# STM32.net
KiCad netlist of a schematic drawn in EasyEDA Pro
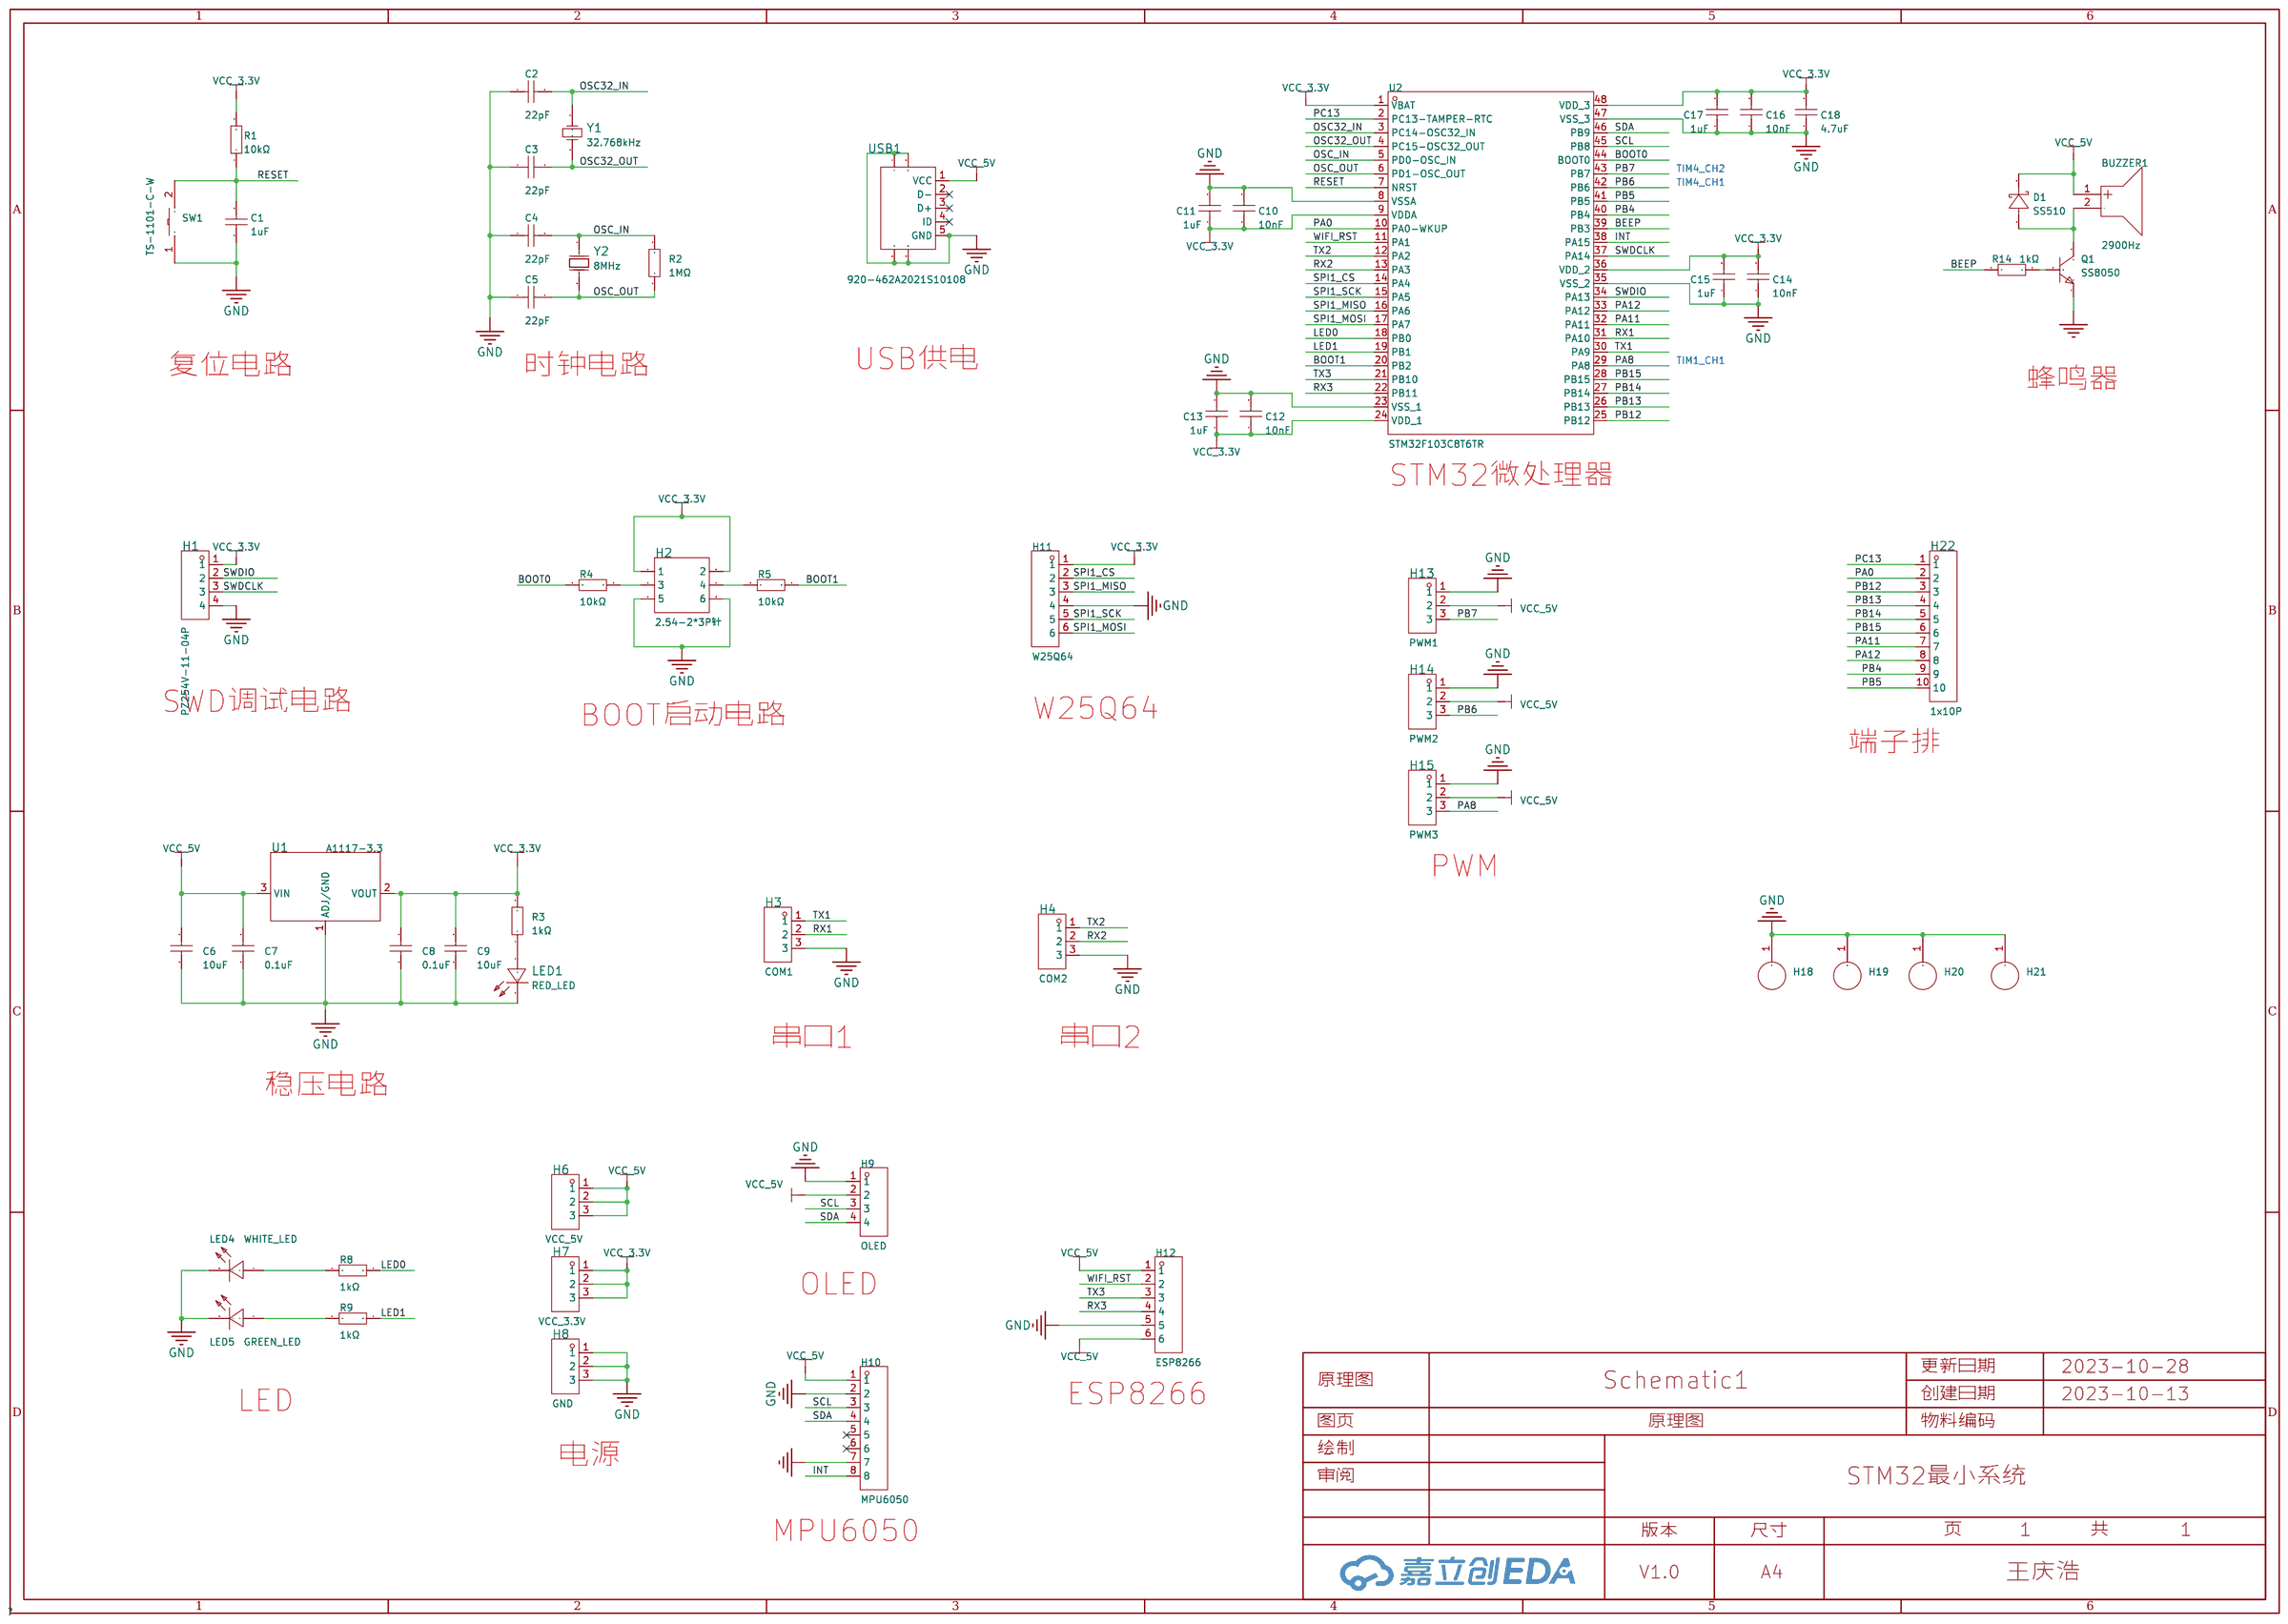
[diagram p0: schematic sheet]

(export (version "E")
  (design (tool "Eeschema 10.0.6"))
  (components
    (comp (ref "BUZZER1")
      (value "2900Hz")
      (footprint "easyedapro:BUZ-TH_BD9.6-P5.00-D0.7-FD")
      (description "驱动方式:有源(内含驱动线路);构造类型:电磁式;额定电压:5V;工作电压:4V~7V;频率:2900Hz;声压(SPL):85dB@5V,10cm;直径(φD):9.6mm;高度:5.5mm;")
      (fields (field (name "Manufacturer Part") "Cy-9650-5029") (field (name "Manufacturer") "CY(超音)"))
      (libsource (lib "easyedapro") (part "CY-9650-5029"))
    )
    (comp (ref "C1")
      (value "1uF")
      (footprint "easyedapro:C0805")
      (description "容值:1uF;精度:±10%;额定电压:50V;材质(温度系数):X7R;")
      (fields
        (field (name "Manufacturer Part") "CL21B105KBFNNNE")
        (field (name "Manufacturer") "SAMSUNG(三星)")
      )
      (libsource (lib "easyedapro") (part "CL21B105KBFNNNE"))
    )
    (comp (ref "C2")
      (value "22pF")
      (footprint "easyedapro:C0805")
      (description "容值:22pF;精度:±5%;额定电压:50V;材质(温度系数):C0G;")
      (fields
        (field (name "Manufacturer Part") "CL21C220JBANNNC")
        (field (name "Manufacturer") "SAMSUNG(三星)")
      )
      (libsource (lib "easyedapro") (part "CL21C220JBANNNC"))
    )
    (comp (ref "C3")
      (value "22pF")
      (footprint "easyedapro:C0805")
      (description "容值:22pF;精度:±5%;额定电压:50V;材质(温度系数):C0G;")
      (fields
        (field (name "Manufacturer Part") "CL21C220JBANNNC")
        (field (name "Manufacturer") "SAMSUNG(三星)")
      )
      (libsource (lib "easyedapro") (part "CL21C220JBANNNC"))
    )
    (comp (ref "C4")
      (value "22pF")
      (footprint "easyedapro:C0805")
      (description "容值:22pF;精度:±5%;额定电压:50V;材质(温度系数):C0G;")
      (fields
        (field (name "Manufacturer Part") "CL21C220JBANNNC")
        (field (name "Manufacturer") "SAMSUNG(三星)")
      )
      (libsource (lib "easyedapro") (part "CL21C220JBANNNC"))
    )
    (comp (ref "C5")
      (value "22pF")
      (footprint "easyedapro:C0805")
      (description "容值:22pF;精度:±5%;额定电压:50V;材质(温度系数):C0G;")
      (fields
        (field (name "Manufacturer Part") "CL21C220JBANNNC")
        (field (name "Manufacturer") "SAMSUNG(三星)")
      )
      (libsource (lib "easyedapro") (part "CL21C220JBANNNC"))
    )
    (comp (ref "C6")
      (value "10uF")
      (footprint "easyedapro:C0805")
      (description "容值:100nF;精度:±10%;额定电压:50V;材质(温度系数):X7R;")
      (fields
        (field (name "Manufacturer Part") "CC0805KRX7R9BB104")
        (field (name "Manufacturer") "YAGEO(国巨)")
      )
      (libsource (lib "easyedapro") (part "CC0805KRX7R9BB104"))
    )
    (comp (ref "C7")
      (value "0.1uF")
      (footprint "easyedapro:C0805")
      (description "容值:100nF;精度:±10%;额定电压:50V;材质(温度系数):X7R;")
      (fields
        (field (name "Manufacturer Part") "CC0805KRX7R9BB104")
        (field (name "Manufacturer") "YAGEO(国巨)")
      )
      (libsource (lib "easyedapro") (part "CC0805KRX7R9BB104"))
    )
    (comp (ref "C8")
      (value "0.1uF")
      (footprint "easyedapro:C0805")
      (description "容值:100nF;精度:±10%;额定电压:50V;材质(温度系数):X7R;")
      (fields
        (field (name "Manufacturer Part") "CC0805KRX7R9BB104")
        (field (name "Manufacturer") "YAGEO(国巨)")
      )
      (libsource (lib "easyedapro") (part "CC0805KRX7R9BB104"))
    )
    (comp (ref "C9")
      (value "10uF")
      (footprint "easyedapro:C0805")
      (description "容值:100nF;精度:±10%;额定电压:50V;材质(温度系数):X7R;")
      (fields
        (field (name "Manufacturer Part") "CC0805KRX7R9BB104")
        (field (name "Manufacturer") "YAGEO(国巨)")
      )
      (libsource (lib "easyedapro") (part "CC0805KRX7R9BB104"))
    )
    (comp (ref "C10")
      (value "10nF")
      (footprint "easyedapro:C0805")
      (description "容值:10nF;精度:±10%;额定电压:50V;材质(温度系数):X7R;")
      (fields (field (name "Manufacturer Part") "0805B103K500NT") (field (name "Manufacturer") "FH(风华)"))
      (libsource (lib "easyedapro") (part "0805B103K500NT"))
    )
    (comp (ref "C11")
      (value "1uF")
      (footprint "easyedapro:C0805")
      (description "容值:1uF;精度:±10%;额定电压:50V;材质(温度系数):X7R;")
      (fields
        (field (name "Manufacturer Part") "CL21B105KBFNNNE")
        (field (name "Manufacturer") "SAMSUNG(三星)")
      )
      (libsource (lib "easyedapro") (part "CL21B105KBFNNNE"))
    )
    (comp (ref "C12")
      (value "10nF")
      (footprint "easyedapro:C0805")
      (description "容值:10nF;精度:±10%;额定电压:50V;材质(温度系数):X7R;")
      (fields (field (name "Manufacturer Part") "0805B103K500NT") (field (name "Manufacturer") "FH(风华)"))
      (libsource (lib "easyedapro") (part "0805B103K500NT"))
    )
    (comp (ref "C13")
      (value "1uF")
      (footprint "easyedapro:C0805")
      (description "容值:1uF;精度:±10%;额定电压:50V;材质(温度系数):X7R;")
      (fields
        (field (name "Manufacturer Part") "CL21B105KBFNNNE")
        (field (name "Manufacturer") "SAMSUNG(三星)")
      )
      (libsource (lib "easyedapro") (part "CL21B105KBFNNNE"))
    )
    (comp (ref "C14")
      (value "10nF")
      (footprint "easyedapro:C0805")
      (description "容值:10nF;精度:±10%;额定电压:50V;材质(温度系数):X7R;")
      (fields (field (name "Manufacturer Part") "0805B103K500NT") (field (name "Manufacturer") "FH(风华)"))
      (libsource (lib "easyedapro") (part "0805B103K500NT"))
    )
    (comp (ref "C15")
      (value "1uF")
      (footprint "easyedapro:C0805")
      (description "容值:1uF;精度:±10%;额定电压:50V;材质(温度系数):X7R;")
      (fields
        (field (name "Manufacturer Part") "CL21B105KBFNNNE")
        (field (name "Manufacturer") "SAMSUNG(三星)")
      )
      (libsource (lib "easyedapro") (part "CL21B105KBFNNNE"))
    )
    (comp (ref "C16")
      (value "10nF")
      (footprint "easyedapro:C0805")
      (description "容值:10nF;精度:±10%;额定电压:50V;材质(温度系数):X7R;")
      (fields (field (name "Manufacturer Part") "0805B103K500NT") (field (name "Manufacturer") "FH(风华)"))
      (libsource (lib "easyedapro") (part "0805B103K500NT"))
    )
    (comp (ref "C17")
      (value "1uF")
      (footprint "easyedapro:C0805")
      (description "容值:1uF;精度:±10%;额定电压:50V;材质(温度系数):X7R;")
      (fields
        (field (name "Manufacturer Part") "CL21B105KBFNNNE")
        (field (name "Manufacturer") "SAMSUNG(三星)")
      )
      (libsource (lib "easyedapro") (part "CL21B105KBFNNNE"))
    )
    (comp (ref "C18")
      (value "4.7uF")
      (footprint "easyedapro:C0805")
      (description "容值:10nF;精度:±10%;额定电压:50V;材质(温度系数):X7R;")
      (fields (field (name "Manufacturer Part") "0805B103K500NT") (field (name "Manufacturer") "FH(风华)"))
      (libsource (lib "easyedapro") (part "0805B103K500NT"))
    )
    (comp (ref "D1")
      (value "SS510")
      (footprint "easyedapro:SMA_L4.3-W2.6-LS5.0-RD")
      (description "二极管配置:独立式;直流反向耐压(Vr):100V;平均整流电流(Io):5A;正向压降(Vf):850mV@5A;反向电流(Ir):500uA@100V;")
      (fields (field (name "Manufacturer") "TWGMC(台湾迪嘉)"))
      (libsource (lib "easyedapro") (part "SS510_C727067"))
    )
    (comp (ref "H1")
      (value "PZ254V-11-04P")
      (footprint "easyedapro:HDR-TH_4P-P2.54-V-M")
      (fields (field (name "Manufacturer") "XFCN(兴飞)"))
      (libsource (lib "easyedapro") (part "PZ254V-11-04P_C2691448"))
    )
    (comp (ref "H2")
      (value "2.54-2*3P针")
      (footprint "easyedapro:HDR-TH_6P-P2.54-V-M-R2-C3-S2.54-1")
      (fields (field (name "Manufacturer") "BOOMELE(博穆精密)"))
      (libsource (lib "easyedapro") (part "Header-Male-2.54_2x3"))
    )
    (comp (ref "H3")
      (value "COM1")
      (footprint "easyedapro:HDR-TH_3P-P2.54-V-M")
      (fields (field (name "Manufacturer") "XFCN(兴飞)"))
      (libsource (lib "easyedapro") (part "PZ254V-11-03P_C2937625"))
    )
    (comp (ref "H4")
      (value "COM2")
      (footprint "easyedapro:HDR-TH_3P-P2.54-V-M")
      (fields (field (name "Manufacturer") "XFCN(兴飞)"))
      (libsource (lib "easyedapro") (part "PZ254V-11-03P_C2937625"))
    )
    (comp (ref "H6")
      (value "VCC_5V")
      (footprint "easyedapro:HDR-TH_3P-P2.54-V-M")
      (fields (field (name "Manufacturer") "XFCN(兴飞)"))
      (libsource (lib "easyedapro") (part "PZ254V-11-03P_C2937625"))
    )
    (comp (ref "H7")
      (value "VCC_3.3V")
      (footprint "easyedapro:HDR-TH_3P-P2.54-V-M")
      (fields (field (name "Manufacturer") "XFCN(兴飞)"))
      (libsource (lib "easyedapro") (part "PZ254V-11-03P_C2937625"))
    )
    (comp (ref "H8")
      (value "GND")
      (footprint "easyedapro:HDR-TH_3P-P2.54-V-M")
      (fields (field (name "Manufacturer") "XFCN(兴飞)"))
      (libsource (lib "easyedapro") (part "PZ254V-11-03P_C2937625"))
    )
    (comp (ref "H9")
      (value "OLED")
      (footprint "easyedapro:HDR-TH_4P-P2.54-V-F")
      (description "排数:单排;总孔位数:4P;间距:2.54mm;插孔结构:1x4P;行距:-;安装类型:直插;塑高:-;触头材质:黄铜;触头镀层:-;")
      (fields (field (name "Manufacturer") "XFCN(兴飞)"))
      (libsource (lib "easyedapro") (part "PM254V-11-04-H85"))
    )
    (comp (ref "H10")
      (value "MPU6050")
      (footprint "easyedapro:HDR-TH_8P-P2.54-V-F")
      (fields (field (name "Manufacturer") "HCTL(华灿天禄)"))
      (libsource (lib "easyedapro") (part "PM254-1-08-Z-8.5"))
    )
    (comp (ref "H11")
      (value "W25Q64")
      (footprint "easyedapro:HDR-TH_6P-P2.54-V-F")
      (fields (field (name "Manufacturer") "XFCN(兴飞)"))
      (libsource (lib "easyedapro") (part "PM254V-11-06-H85"))
    )
    (comp (ref "H12")
      (value "ESP8266")
      (footprint "easyedapro:HDR-TH_6P-P2.54-V-F")
      (fields (field (name "Manufacturer") "XFCN(兴飞)"))
      (libsource (lib "easyedapro") (part "PM254V-11-06-H85"))
    )
    (comp (ref "H13")
      (value "PWM1")
      (footprint "easyedapro:HDR-TH_3P-P2.54-V-M")
      (fields (field (name "Manufacturer") "XFCN(兴飞)"))
      (libsource (lib "easyedapro") (part "PZ254V-11-03P_C2937625"))
    )
    (comp (ref "H14")
      (value "PWM2")
      (footprint "easyedapro:HDR-TH_3P-P2.54-V-M")
      (fields (field (name "Manufacturer") "XFCN(兴飞)"))
      (libsource (lib "easyedapro") (part "PZ254V-11-03P_C2937625"))
    )
    (comp (ref "H15")
      (value "PWM3")
      (footprint "easyedapro:HDR-TH_3P-P2.54-V-M")
      (fields (field (name "Manufacturer") "XFCN(兴飞)"))
      (libsource (lib "easyedapro") (part "PZ254V-11-03P_C2937625"))
    )
    (comp (ref "H18")
      (value "~")
      (footprint "easyedapro:固定孔封装")
      (description "铜柱孔")
      (libsource (lib "easyedapro") (part "固定孔"))
    )
    (comp (ref "H19")
      (value "~")
      (footprint "easyedapro:固定孔封装")
      (description "铜柱孔")
      (libsource (lib "easyedapro") (part "固定孔"))
    )
    (comp (ref "H20")
      (value "~")
      (footprint "easyedapro:固定孔封装")
      (description "铜柱孔")
      (libsource (lib "easyedapro") (part "固定孔"))
    )
    (comp (ref "H21")
      (value "~")
      (footprint "easyedapro:固定孔封装")
      (description "铜柱孔")
      (libsource (lib "easyedapro") (part "固定孔"))
    )
    (comp (ref "H22")
      (value "1x10P")
      (footprint "easyedapro:HDR-TH_10P-P2.54-V-M")
      (fields (field (name "Manufacturer") "XFCN(兴飞)"))
      (libsource (lib "easyedapro") (part "PZ254V-11-10P"))
    )
    (comp (ref "LED1")
      (value "RED_LED")
      (footprint "easyedapro:LED1206-R-RD_RED")
      (description "发光颜色:红灯;")
      (fields (field (name "Manufacturer") "国星光电"))
      (libsource (lib "easyedapro") (part "FC-3215HRK-620D"))
    )
    (comp (ref "LED4")
      (value "WHITE_LED")
      (footprint "easyedapro:LED0805-R-RD")
      (description "发光颜色:红灯;")
      (fields (field (name "Manufacturer") "国星光电"))
      (libsource (lib "easyedapro") (part "FC-2012HRK-620D"))
    )
    (comp (ref "LED5")
      (value "GREEN_LED")
      (footprint "easyedapro:LED0805-R-RD")
      (description "发光颜色:红灯;")
      (fields (field (name "Manufacturer") "国星光电"))
      (libsource (lib "easyedapro") (part "FC-2012HRK-620D"))
    )
    (comp (ref "Q1")
      (value "SS8050")
      (footprint "easyedapro:SOT-23-3_L2.9-W1.3-P1.90-LS2.4-BR")
      (description "晶体管类型:NPN;集射极击穿电压(Vceo):25V;集电极电流(Ic):1.5A;功率(Pd):300mW;直流电流增益(hFE@Ic,Vce):200@100mA,1V;")
      (fields (field (name "Manufacturer") "CJ(江苏长电/长晶)"))
      (libsource (lib "easyedapro") (part "SS8050_C2150"))
    )
    (comp (ref "R1")
      (value "10kΩ")
      (footprint "easyedapro:R0805")
      (description "电阻类型:厚膜电阻;阻值:10kΩ;精度:±1%;功率:125mW;")
      (fields
        (field (name "Manufacturer Part") "0805W8F1002T5E")
        (field (name "Manufacturer") "UNI-ROYAL(厚声)")
      )
      (libsource (lib "easyedapro") (part "0805W8F1002T5E"))
    )
    (comp (ref "R2")
      (value "1MΩ")
      (footprint "easyedapro:R0805")
      (description "电阻类型:厚膜电阻;阻值:1MΩ;精度:±1%;功率:125mW;")
      (fields
        (field (name "Manufacturer Part") "0805W8F1004T5E")
        (field (name "Manufacturer") "UNI-ROYAL(厚声)")
      )
      (libsource (lib "easyedapro") (part "0805W8F1004T5E"))
    )
    (comp (ref "R3")
      (value "1kΩ")
      (footprint "easyedapro:R0805")
      (description "电阻类型:厚膜电阻;阻值:1kΩ;精度:±1%;功率:125mW;")
      (fields
        (field (name "Manufacturer Part") "0805W8F1001T5E")
        (field (name "Manufacturer") "UNI-ROYAL(厚声)")
      )
      (libsource (lib "easyedapro") (part "0805W8F1001T5E"))
    )
    (comp (ref "R4")
      (value "10kΩ")
      (footprint "easyedapro:R0805")
      (description "电阻类型:厚膜电阻;阻值:10kΩ;精度:±1%;功率:125mW;")
      (fields
        (field (name "Manufacturer Part") "0805W8F1002T5E")
        (field (name "Manufacturer") "UNI-ROYAL(厚声)")
      )
      (libsource (lib "easyedapro") (part "0805W8F1002T5E"))
    )
    (comp (ref "R5")
      (value "10kΩ")
      (footprint "easyedapro:R0805")
      (description "电阻类型:厚膜电阻;阻值:10kΩ;精度:±1%;功率:125mW;")
      (fields
        (field (name "Manufacturer Part") "0805W8F1002T5E")
        (field (name "Manufacturer") "UNI-ROYAL(厚声)")
      )
      (libsource (lib "easyedapro") (part "0805W8F1002T5E"))
    )
    (comp (ref "R8")
      (value "1kΩ")
      (footprint "easyedapro:R0805")
      (description "电阻类型:厚膜电阻;阻值:1kΩ;精度:±1%;功率:125mW;")
      (fields
        (field (name "Manufacturer Part") "0805W8F1001T5E")
        (field (name "Manufacturer") "UNI-ROYAL(厚声)")
      )
      (libsource (lib "easyedapro") (part "0805W8F1001T5E"))
    )
    (comp (ref "R9")
      (value "1kΩ")
      (footprint "easyedapro:R0805")
      (description "电阻类型:厚膜电阻;阻值:1kΩ;精度:±1%;功率:125mW;")
      (fields
        (field (name "Manufacturer Part") "0805W8F1001T5E")
        (field (name "Manufacturer") "UNI-ROYAL(厚声)")
      )
      (libsource (lib "easyedapro") (part "0805W8F1001T5E"))
    )
    (comp (ref "R14")
      (value "1kΩ")
      (footprint "easyedapro:R0805")
      (description "电阻类型:厚膜电阻;阻值:1kΩ;精度:±1%;功率:125mW;")
      (fields
        (field (name "Manufacturer Part") "0805W8F1001T5E")
        (field (name "Manufacturer") "UNI-ROYAL(厚声)")
      )
      (libsource (lib "easyedapro") (part "0805W8F1001T5E"))
    )
    (comp (ref "SW1")
      (value "TS-1101-C-W")
      (footprint "easyedapro:SW-SMD_L6.0-W3.3-LS8.0")
      (description "触点电流:50mA;额定电压(AC):-;额定电压(DC):12V;额定功率:-;绝缘电阻:-;电路结构:单刀单掷;安装方式:立贴;带灯:无;作用力:260gf;机械寿命:5万次;带支架:否;")
      (fields (field (name "Manufacturer") "XKB Connectivity(中国星坤)"))
      (libsource (lib "easyedapro") (part "TS-1101-C-W"))
    )
    (comp (ref "U1")
      (value "A1117-3.3")
      (footprint "easyedapro:SOT-223-3_L6.5-W3.4-P2.30-LS7.0-BR-1")
      (fields (field (name "Manufacturer") "IDCHIP(英锐芯)"))
      (libsource (lib "easyedapro") (part "A1117-3.3"))
    )
    (comp (ref "U2")
      (value "STM32F103C8T6TR")
      (footprint "easyedapro:LQFP-48_L7.0-W7.0-P0.50-LS9.0-BL")
      (fields (field (name "Manufacturer") "ST(意法半导体)"))
      (libsource (lib "easyedapro") (part "STM32F103C8T6TR"))
    )
    (comp (ref "USB1")
      (value "920-462A2021S10108")
      (footprint "easyedapro:MINI-USB-SMD_C105424")
      (description "连接器类型:Mini-B;标准:USB 2.0;公母:母座;触点数量:5P;端口数量:1;")
      (fields (field (name "Manufacturer") "精拓金"))
      (libsource (lib "easyedapro") (part "USB-MINI-SMD-9.2X9.4-H3.7"))
    )
    (comp (ref "Y1")
      (value "32.768kHz")
      (footprint "easyedapro:OSC-TH_BD3.1-P0.8-D0.3")
      (description "频率:32.768kHz;频率公差:±10ppm;负载电容:12.5pF;")
      (fields (field (name "Manufacturer Part") "X308032768KGB2SC") (field (name "Manufacturer") "YXC(扬兴晶振)"))
      (libsource (lib "easyedapro") (part "X308032768KGB2SC"))
    )
    (comp (ref "Y2")
      (value "8MHz")
      (footprint "easyedapro:OSC-TH_L10.0-W4.5-P5.00")
      (description "频率:8MHz;频率公差:±20ppm;负载电容:20pF;")
      (fields (field (name "Manufacturer Part") "X49SD8MSD2SC") (field (name "Manufacturer") "YXC(扬兴晶振)"))
      (libsource (lib "easyedapro") (part "X49SD8MSD2SC"))
    )
  )
  (nets
    (net (code "1") (name "/BEEP") (class "Default")
      (node (ref "R14") (pin "2") (pinfunction "2_2") (pintype "input"))
      (node (ref "U2") (pin "39") (pinfunction "PB3_39") (pintype "input"))
    )
    (net (code "2") (name "/BOOT0") (class "Default")
      (node (ref "R4") (pin "1") (pinfunction "1_1") (pintype "input"))
      (node (ref "U2") (pin "44") (pinfunction "BOOT0_44") (pintype "input"))
    )
    (net (code "3") (name "/BOOT1") (class "Default")
      (node (ref "R5") (pin "2") (pinfunction "2_2") (pintype "input"))
      (node (ref "U2") (pin "20") (pinfunction "PB2_20") (pintype "input"))
    )
    (net (code "4") (name "/INT") (class "Default")
      (node (ref "H10") (pin "8") (pinfunction "8_8") (pintype "unspecified"))
      (node (ref "U2") (pin "38") (pinfunction "PA15_38") (pintype "input"))
    )
    (net (code "5") (name "/LED0") (class "Default")
      (node (ref "R8") (pin "1") (pinfunction "1_1") (pintype "input"))
      (node (ref "U2") (pin "18") (pinfunction "PB0_18") (pintype "input"))
    )
    (net (code "6") (name "/LED1") (class "Default")
      (node (ref "R9") (pin "1") (pinfunction "1_1") (pintype "input"))
      (node (ref "U2") (pin "19") (pinfunction "PB1_19") (pintype "input"))
    )
    (net (code "7") (name "/OSC32_IN") (class "Default")
      (node (ref "C2") (pin "2") (pinfunction "2_2") (pintype "input"))
      (node (ref "U2") (pin "3") (pinfunction "PC14-OSC32_IN_3") (pintype "input"))
      (node (ref "Y1") (pin "2") (pinfunction "OSC2_2") (pintype "input"))
    )
    (net (code "8") (name "/OSC32_OUT") (class "Default")
      (node (ref "C3") (pin "2") (pinfunction "2_2") (pintype "input"))
      (node (ref "U2") (pin "4") (pinfunction "PC15-OSC32_OUT_4") (pintype "input"))
      (node (ref "Y1") (pin "1") (pinfunction "OSC1_1") (pintype "input"))
    )
    (net (code "9") (name "/OSC_IN") (class "Default")
      (node (ref "C4") (pin "2") (pinfunction "2_2") (pintype "input"))
      (node (ref "R2") (pin "2") (pinfunction "2_2") (pintype "input"))
      (node (ref "U2") (pin "5") (pinfunction "PD0-OSC_IN_5") (pintype "input"))
      (node (ref "Y2") (pin "1") (pinfunction "OSC1_1") (pintype "input"))
    )
    (net (code "10") (name "/OSC_OUT") (class "Default")
      (node (ref "C5") (pin "2") (pinfunction "2_2") (pintype "input"))
      (node (ref "R2") (pin "1") (pinfunction "1_1") (pintype "input"))
      (node (ref "U2") (pin "6") (pinfunction "PD1-OSC_OUT_6") (pintype "input"))
      (node (ref "Y2") (pin "2") (pinfunction "OSC2_2") (pintype "input"))
    )
    (net (code "11") (name "/PA0") (class "Default")
      (node (ref "H22") (pin "2") (pinfunction "2_2") (pintype "input"))
      (node (ref "U2") (pin "10") (pinfunction "PA0-WKUP_10") (pintype "input"))
    )
    (net (code "12") (name "/PA8") (class "Default")
      (node (ref "H15") (pin "3") (pinfunction "3_3") (pintype "input"))
      (node (ref "U2") (pin "29") (pinfunction "PA8_29") (pintype "input"))
    )
    (net (code "13") (name "/PA11") (class "Default")
      (node (ref "H22") (pin "7") (pinfunction "7_7") (pintype "input"))
      (node (ref "U2") (pin "32") (pinfunction "PA11_32") (pintype "input"))
    )
    (net (code "14") (name "/PA12") (class "Default")
      (node (ref "H22") (pin "8") (pinfunction "8_8") (pintype "input"))
      (node (ref "U2") (pin "33") (pinfunction "PA12_33") (pintype "input"))
    )
    (net (code "15") (name "/PB4") (class "Default")
      (node (ref "H22") (pin "9") (pinfunction "9_9") (pintype "input"))
      (node (ref "U2") (pin "40") (pinfunction "PB4_40") (pintype "input"))
    )
    (net (code "16") (name "/PB5") (class "Default")
      (node (ref "H22") (pin "10") (pinfunction "10_10") (pintype "input"))
      (node (ref "U2") (pin "41") (pinfunction "PB5_41") (pintype "input"))
    )
    (net (code "17") (name "/PB6") (class "Default")
      (node (ref "H14") (pin "3") (pinfunction "3_3") (pintype "input"))
      (node (ref "U2") (pin "42") (pinfunction "PB6_42") (pintype "input"))
    )
    (net (code "18") (name "/PB7") (class "Default")
      (node (ref "H13") (pin "3") (pinfunction "3_3") (pintype "input"))
      (node (ref "U2") (pin "43") (pinfunction "PB7_43") (pintype "input"))
    )
    (net (code "19") (name "/PB12") (class "Default")
      (node (ref "H22") (pin "3") (pinfunction "3_3") (pintype "input"))
      (node (ref "U2") (pin "25") (pinfunction "PB12_25") (pintype "input"))
    )
    (net (code "20") (name "/PB13") (class "Default")
      (node (ref "H22") (pin "4") (pinfunction "4_4") (pintype "input"))
      (node (ref "U2") (pin "26") (pinfunction "PB13_26") (pintype "input"))
    )
    (net (code "21") (name "/PB14") (class "Default")
      (node (ref "H22") (pin "5") (pinfunction "5_5") (pintype "input"))
      (node (ref "U2") (pin "27") (pinfunction "PB14_27") (pintype "input"))
    )
    (net (code "22") (name "/PB15") (class "Default")
      (node (ref "H22") (pin "6") (pinfunction "6_6") (pintype "input"))
      (node (ref "U2") (pin "28") (pinfunction "PB15_28") (pintype "input"))
    )
    (net (code "23") (name "/PC13") (class "Default")
      (node (ref "H22") (pin "1") (pinfunction "1_1") (pintype "input"))
      (node (ref "U2") (pin "2") (pinfunction "PC13-TAMPER-RTC_2") (pintype "input"))
    )
    (net (code "24") (name "/RESET") (class "Default")
      (node (ref "C1") (pin "2") (pinfunction "2_2") (pintype "input"))
      (node (ref "R1") (pin "1") (pinfunction "1_1") (pintype "input"))
      (node (ref "SW1") (pin "2") (pinfunction "2_2") (pintype "input"))
      (node (ref "U2") (pin "7") (pinfunction "NRST_7") (pintype "input"))
    )
    (net (code "25") (name "/RX1") (class "Default")
      (node (ref "H3") (pin "2") (pinfunction "2_2") (pintype "input"))
      (node (ref "U2") (pin "31") (pinfunction "PA10_31") (pintype "input"))
    )
    (net (code "26") (name "/RX2") (class "Default")
      (node (ref "H4") (pin "2") (pinfunction "2_2") (pintype "input"))
      (node (ref "U2") (pin "13") (pinfunction "PA3_13") (pintype "input"))
    )
    (net (code "27") (name "/RX3") (class "Default")
      (node (ref "H12") (pin "4") (pinfunction "4_4") (pintype "unspecified"))
      (node (ref "U2") (pin "22") (pinfunction "PB11_22") (pintype "input"))
    )
    (net (code "28") (name "/SCL") (class "Default")
      (node (ref "H10") (pin "3") (pinfunction "3_3") (pintype "unspecified"))
      (node (ref "H9") (pin "3") (pinfunction "3_3") (pintype "unspecified"))
      (node (ref "U2") (pin "45") (pinfunction "PB8_45") (pintype "input"))
    )
    (net (code "29") (name "/SDA") (class "Default")
      (node (ref "H10") (pin "4") (pinfunction "4_4") (pintype "unspecified"))
      (node (ref "H9") (pin "4") (pinfunction "4_4") (pintype "unspecified"))
      (node (ref "U2") (pin "46") (pinfunction "PB9_46") (pintype "input"))
    )
    (net (code "30") (name "/SPI1_CS") (class "Default")
      (node (ref "H11") (pin "2") (pinfunction "2_2") (pintype "unspecified"))
      (node (ref "U2") (pin "14") (pinfunction "PA4_14") (pintype "input"))
    )
    (net (code "31") (name "/SPI1_MISO") (class "Default")
      (node (ref "H11") (pin "3") (pinfunction "3_3") (pintype "unspecified"))
      (node (ref "U2") (pin "16") (pinfunction "PA6_16") (pintype "input"))
    )
    (net (code "32") (name "/SPI1_MOSI") (class "Default")
      (node (ref "H11") (pin "6") (pinfunction "6_6") (pintype "unspecified"))
      (node (ref "U2") (pin "17") (pinfunction "PA7_17") (pintype "input"))
    )
    (net (code "33") (name "/SPI1_SCK") (class "Default")
      (node (ref "H11") (pin "5") (pinfunction "5_5") (pintype "unspecified"))
      (node (ref "U2") (pin "15") (pinfunction "PA5_15") (pintype "input"))
    )
    (net (code "34") (name "/SWDCLK") (class "Default")
      (node (ref "H1") (pin "3") (pinfunction "3_3") (pintype "input"))
      (node (ref "U2") (pin "37") (pinfunction "PA14_37") (pintype "input"))
    )
    (net (code "35") (name "/SWDIO") (class "Default")
      (node (ref "H1") (pin "2") (pinfunction "2_2") (pintype "input"))
      (node (ref "U2") (pin "34") (pinfunction "PA13_34") (pintype "input"))
    )
    (net (code "36") (name "/TX1") (class "Default")
      (node (ref "H3") (pin "1") (pinfunction "1_1") (pintype "input"))
      (node (ref "U2") (pin "30") (pinfunction "PA9_30") (pintype "input"))
    )
    (net (code "37") (name "/TX2") (class "Default")
      (node (ref "H4") (pin "1") (pinfunction "1_1") (pintype "input"))
      (node (ref "U2") (pin "12") (pinfunction "PA2_12") (pintype "input"))
    )
    (net (code "38") (name "/TX3") (class "Default")
      (node (ref "H12") (pin "3") (pinfunction "3_3") (pintype "unspecified"))
      (node (ref "U2") (pin "21") (pinfunction "PB10_21") (pintype "input"))
    )
    (net (code "39") (name "/WIFI_RST") (class "Default")
      (node (ref "H12") (pin "2") (pinfunction "2_2") (pintype "unspecified"))
      (node (ref "U2") (pin "11") (pinfunction "PA1_11") (pintype "input"))
    )
    (net (code "40") (name "GND") (class "Default")
      (node (ref "C1") (pin "1") (pinfunction "1_1") (pintype "input"))
      (node (ref "C10") (pin "2") (pinfunction "2_2") (pintype "input"))
      (node (ref "C11") (pin "2") (pinfunction "2_2") (pintype "input"))
      (node (ref "C12") (pin "2") (pinfunction "2_2") (pintype "input"))
      (node (ref "C13") (pin "2") (pinfunction "2_2") (pintype "input"))
      (node (ref "C14") (pin "1") (pinfunction "1_1") (pintype "input"))
      (node (ref "C15") (pin "1") (pinfunction "1_1") (pintype "input"))
      (node (ref "C16") (pin "1") (pinfunction "1_1") (pintype "input"))
      (node (ref "C17") (pin "1") (pinfunction "1_1") (pintype "input"))
      (node (ref "C18") (pin "1") (pinfunction "1_1") (pintype "input"))
      (node (ref "C2") (pin "1") (pinfunction "1_1") (pintype "input"))
      (node (ref "C3") (pin "1") (pinfunction "1_1") (pintype "input"))
      (node (ref "C4") (pin "1") (pinfunction "1_1") (pintype "input"))
      (node (ref "C5") (pin "1") (pinfunction "1_1") (pintype "input"))
      (node (ref "C6") (pin "1") (pinfunction "1_1") (pintype "input"))
      (node (ref "C7") (pin "1") (pinfunction "1_1") (pintype "input"))
      (node (ref "C8") (pin "1") (pinfunction "1_1") (pintype "input"))
      (node (ref "C9") (pin "1") (pinfunction "1_1") (pintype "input"))
      (node (ref "H1") (pin "4") (pinfunction "4_4") (pintype "input"))
      (node (ref "H10") (pin "2") (pinfunction "2_2") (pintype "unspecified"))
      (node (ref "H10") (pin "7") (pinfunction "7_7") (pintype "unspecified"))
      (node (ref "H11") (pin "4") (pinfunction "4_4") (pintype "unspecified"))
      (node (ref "H12") (pin "5") (pinfunction "5_5") (pintype "unspecified"))
      (node (ref "H13") (pin "1") (pinfunction "1_1") (pintype "input"))
      (node (ref "H14") (pin "1") (pinfunction "1_1") (pintype "input"))
      (node (ref "H15") (pin "1") (pinfunction "1_1") (pintype "input"))
      (node (ref "H18") (pin "1") (pinfunction "1_1") (pintype "bidirectional"))
      (node (ref "H19") (pin "1") (pinfunction "1_1") (pintype "bidirectional"))
      (node (ref "H2") (pin "5") (pinfunction "5_5") (pintype "input"))
      (node (ref "H2") (pin "6") (pinfunction "6_6") (pintype "input"))
      (node (ref "H20") (pin "1") (pinfunction "1_1") (pintype "bidirectional"))
      (node (ref "H21") (pin "1") (pinfunction "1_1") (pintype "bidirectional"))
      (node (ref "H3") (pin "3") (pinfunction "3_3") (pintype "input"))
      (node (ref "H4") (pin "3") (pinfunction "3_3") (pintype "input"))
      (node (ref "H8") (pin "1") (pinfunction "1_1") (pintype "input"))
      (node (ref "H8") (pin "2") (pinfunction "2_2") (pintype "input"))
      (node (ref "H8") (pin "3") (pinfunction "3_3") (pintype "input"))
      (node (ref "H9") (pin "1") (pinfunction "1_1") (pintype "unspecified"))
      (node (ref "LED1") (pin "2") (pinfunction "K_2") (pintype "input"))
      (node (ref "LED4") (pin "2") (pinfunction "-_2") (pintype "unspecified"))
      (node (ref "LED5") (pin "2") (pinfunction "-_2") (pintype "unspecified"))
      (node (ref "Q1") (pin "2") (pinfunction "E_2") (pintype "input"))
      (node (ref "SW1") (pin "1") (pinfunction "1_1") (pintype "input"))
      (node (ref "U1") (pin "1") (pinfunction "ADJ/GND_1") (pintype "input"))
      (node (ref "U2") (pin "23") (pinfunction "VSS_1_23") (pintype "input"))
      (node (ref "U2") (pin "35") (pinfunction "VSS_2_35") (pintype "input"))
      (node (ref "U2") (pin "47") (pinfunction "VSS_3_47") (pintype "input"))
      (node (ref "U2") (pin "8") (pinfunction "VSSA_8") (pintype "input"))
      (node (ref "USB1") (pin "5") (pinfunction "GND_5") (pintype "input"))
      (node (ref "USB1") (pin "6") (pinfunction "6_6") (pintype "input"))
      (node (ref "USB1") (pin "7") (pinfunction "7_7") (pintype "input"))
      (node (ref "USB1") (pin "8") (pinfunction "8_8") (pintype "input"))
      (node (ref "USB1") (pin "9") (pinfunction "9_9") (pintype "input"))
    )
    (net (code "41") (name "Net-(BUZZER1--)") (class "Default")
      (node (ref "BUZZER1") (pin "2") (pinfunction "-_2") (pintype "input"))
      (node (ref "D1") (pin "2") (pinfunction "A_2") (pintype "input"))
      (node (ref "Q1") (pin "3") (pinfunction "C_3") (pintype "input"))
    )
    (net (code "42") (name "Net-(H2-Pad3)") (class "Default")
      (node (ref "H2") (pin "3") (pinfunction "3_3") (pintype "input"))
      (node (ref "R4") (pin "2") (pinfunction "2_2") (pintype "input"))
    )
    (net (code "43") (name "Net-(H2-Pad4)") (class "Default")
      (node (ref "H2") (pin "4") (pinfunction "4_4") (pintype "input"))
      (node (ref "R5") (pin "1") (pinfunction "1_1") (pintype "input"))
    )
    (net (code "44") (name "Net-(LED1-A)") (class "Default")
      (node (ref "LED1") (pin "1") (pinfunction "A_1") (pintype "input"))
      (node (ref "R3") (pin "1") (pinfunction "1_1") (pintype "input"))
    )
    (net (code "45") (name "Net-(LED4-+)") (class "Default")
      (node (ref "LED4") (pin "1") (pinfunction "+_1") (pintype "unspecified"))
      (node (ref "R8") (pin "2") (pinfunction "2_2") (pintype "input"))
    )
    (net (code "46") (name "Net-(LED5-+)") (class "Default")
      (node (ref "LED5") (pin "1") (pinfunction "+_1") (pintype "unspecified"))
      (node (ref "R9") (pin "2") (pinfunction "2_2") (pintype "input"))
    )
    (net (code "47") (name "Net-(Q1-B)") (class "Default")
      (node (ref "Q1") (pin "1") (pinfunction "B_1") (pintype "input"))
      (node (ref "R14") (pin "1") (pinfunction "1_1") (pintype "input"))
    )
    (net (code "48") (name "VCC_3.3V") (class "Default")
      (node (ref "C10") (pin "1") (pinfunction "1_1") (pintype "input"))
      (node (ref "C11") (pin "1") (pinfunction "1_1") (pintype "input"))
      (node (ref "C12") (pin "1") (pinfunction "1_1") (pintype "input"))
      (node (ref "C13") (pin "1") (pinfunction "1_1") (pintype "input"))
      (node (ref "C14") (pin "2") (pinfunction "2_2") (pintype "input"))
      (node (ref "C15") (pin "2") (pinfunction "2_2") (pintype "input"))
      (node (ref "C16") (pin "2") (pinfunction "2_2") (pintype "input"))
      (node (ref "C17") (pin "2") (pinfunction "2_2") (pintype "input"))
      (node (ref "C18") (pin "2") (pinfunction "2_2") (pintype "input"))
      (node (ref "C8") (pin "2") (pinfunction "2_2") (pintype "input"))
      (node (ref "C9") (pin "2") (pinfunction "2_2") (pintype "input"))
      (node (ref "H1") (pin "1") (pinfunction "1_1") (pintype "input"))
      (node (ref "H11") (pin "1") (pinfunction "1_1") (pintype "unspecified"))
      (node (ref "H2") (pin "1") (pinfunction "1_1") (pintype "input"))
      (node (ref "H2") (pin "2") (pinfunction "2_2") (pintype "input"))
      (node (ref "H7") (pin "1") (pinfunction "1_1") (pintype "input"))
      (node (ref "H7") (pin "2") (pinfunction "2_2") (pintype "input"))
      (node (ref "H7") (pin "3") (pinfunction "3_3") (pintype "input"))
      (node (ref "R1") (pin "2") (pinfunction "2_2") (pintype "input"))
      (node (ref "R3") (pin "2") (pinfunction "2_2") (pintype "input"))
      (node (ref "U1") (pin "2") (pinfunction "VOUT_2") (pintype "input"))
      (node (ref "U2") (pin "1") (pinfunction "VBAT_1") (pintype "input"))
      (node (ref "U2") (pin "24") (pinfunction "VDD_1_24") (pintype "input"))
      (node (ref "U2") (pin "36") (pinfunction "VDD_2_36") (pintype "input"))
      (node (ref "U2") (pin "48") (pinfunction "VDD_3_48") (pintype "input"))
      (node (ref "U2") (pin "9") (pinfunction "VDDA_9") (pintype "input"))
    )
    (net (code "49") (name "VCC_5V") (class "Default")
      (node (ref "BUZZER1") (pin "1") (pinfunction "+_1") (pintype "input"))
      (node (ref "C6") (pin "2") (pinfunction "2_2") (pintype "input"))
      (node (ref "C7") (pin "2") (pinfunction "2_2") (pintype "input"))
      (node (ref "D1") (pin "1") (pinfunction "K_1") (pintype "input"))
      (node (ref "H10") (pin "1") (pinfunction "1_1") (pintype "unspecified"))
      (node (ref "H12") (pin "1") (pinfunction "1_1") (pintype "unspecified"))
      (node (ref "H12") (pin "6") (pinfunction "6_6") (pintype "unspecified"))
      (node (ref "H13") (pin "2") (pinfunction "2_2") (pintype "input"))
      (node (ref "H14") (pin "2") (pinfunction "2_2") (pintype "input"))
      (node (ref "H15") (pin "2") (pinfunction "2_2") (pintype "input"))
      (node (ref "H6") (pin "1") (pinfunction "1_1") (pintype "input"))
      (node (ref "H6") (pin "2") (pinfunction "2_2") (pintype "input"))
      (node (ref "H6") (pin "3") (pinfunction "3_3") (pintype "input"))
      (node (ref "H9") (pin "2") (pinfunction "2_2") (pintype "unspecified"))
      (node (ref "U1") (pin "3") (pinfunction "VIN_3") (pintype "input"))
      (node (ref "USB1") (pin "1") (pinfunction "VCC_1") (pintype "input"))
    )
    (net (code "50") (name "unconnected-(H10-Pad5)") (class "Default")
      (node (ref "H10") (pin "5") (pinfunction "5_5") (pintype "unspecified+no_connect"))
    )
    (net (code "51") (name "unconnected-(H10-Pad6)") (class "Default")
      (node (ref "H10") (pin "6") (pinfunction "6_6") (pintype "unspecified+no_connect"))
    )
    (net (code "52") (name "unconnected-(USB1-D+-Pad3)") (class "Default")
      (node (ref "USB1") (pin "3") (pinfunction "D+_3") (pintype "input+no_connect"))
    )
    (net (code "53") (name "unconnected-(USB1-D--Pad2)") (class "Default")
      (node (ref "USB1") (pin "2") (pinfunction "D-_2") (pintype "input+no_connect"))
    )
    (net (code "54") (name "unconnected-(USB1-ID-Pad4)") (class "Default")
      (node (ref "USB1") (pin "4") (pinfunction "ID_4") (pintype "input+no_connect"))
    )
  )
)
